# avoccado-nora-panel-teardropped.net
KiCad netlist of a schematic drawn in EAGLE
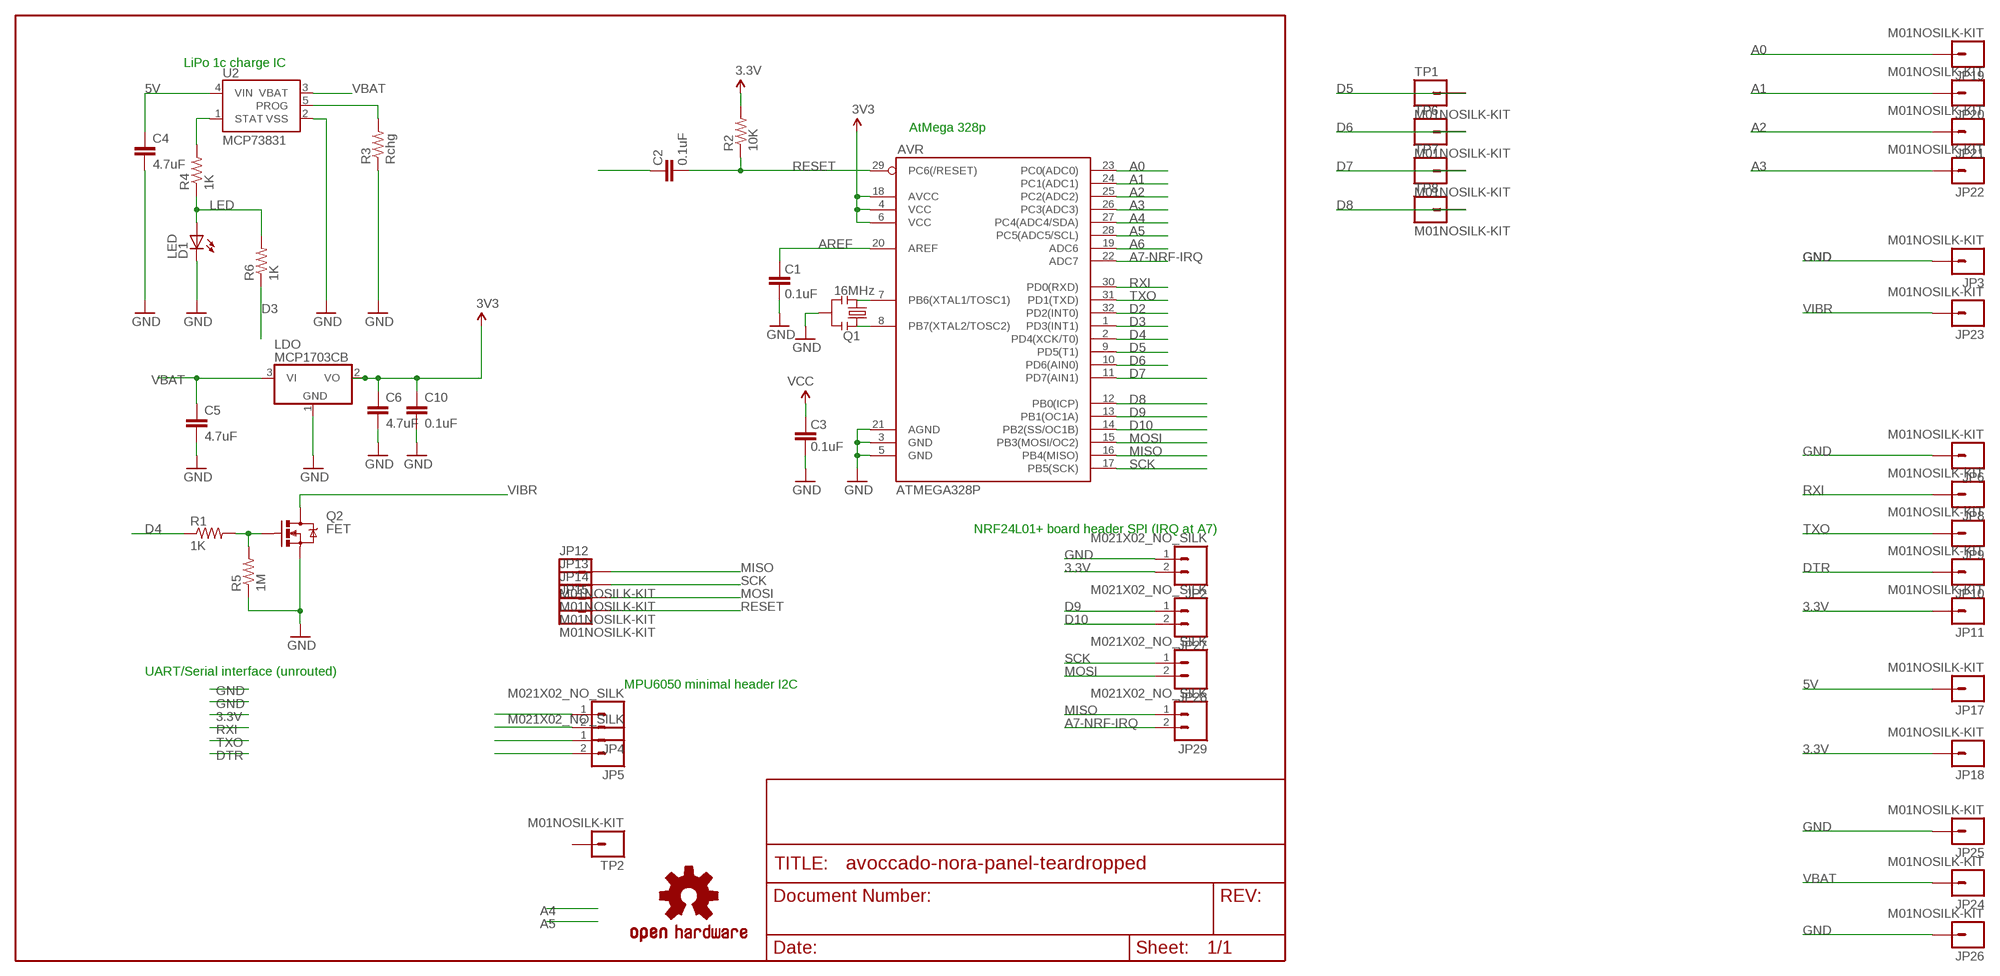
[diagram p0: schematic, sheet 1]

(export (version "E")
  (design (tool "Eeschema 10.0.6"))
  (components
    (comp (ref "AVR")
      (value "ATMEGA328P")
      (footprint "eagle-import:TQFP32-08")
      (libsource (lib "eagle-import") (part "ATMEGA328_SMT"))
    )
    (comp (ref "C1")
      (value "0.1uF")
      (footprint "eagle-import:C0402")
      (libsource (lib "eagle-import") (part "CAP0402"))
    )
    (comp (ref "C2")
      (value "0.1uF")
      (footprint "eagle-import:C0402")
      (libsource (lib "eagle-import") (part "CAP0402"))
    )
    (comp (ref "C3")
      (value "0.1uF")
      (footprint "eagle-import:C0402")
      (libsource (lib "eagle-import") (part "CAP0402"))
    )
    (comp (ref "C4")
      (value "4.7uF")
      (footprint "eagle-import:0603-CAP")
      (libsource (lib "eagle-import") (part "4.7UF-6.3V-10%(0603)0603"))
    )
    (comp (ref "C5")
      (value "4.7uF")
      (footprint "eagle-import:0603-CAP")
      (libsource (lib "eagle-import") (part "4.7UF-6.3V-10%(0603)0603"))
    )
    (comp (ref "C6")
      (value "4.7uF")
      (footprint "eagle-import:0603-CAP")
      (libsource (lib "eagle-import") (part "4.7UF-6.3V-10%(0603)0603"))
    )
    (comp (ref "C10")
      (value "0.1uF")
      (footprint "eagle-import:C0402")
      (libsource (lib "eagle-import") (part "CAP0402"))
    )
    (comp (ref "D1")
      (value "LED")
      (footprint "eagle-import:LED-0603")
      (libsource (lib "eagle-import") (part "LED0603"))
    )
    (comp (ref "JP2")
      (value "M021X02_NO_SILK")
      (footprint "eagle-import:1X02_NO_SILK")
      (libsource (lib "eagle-import") (part "M021X02_NO_SILK"))
    )
    (comp (ref "JP3")
      (value "M01NOSILK-KIT")
      (footprint "eagle-import:1X01NS-KIT")
      (libsource (lib "eagle-import") (part "M01NOSILK-KIT"))
    )
    (comp (ref "JP4")
      (value "M021X02_NO_SILK")
      (footprint "eagle-import:1X02_NO_SILK")
      (libsource (lib "eagle-import") (part "M021X02_NO_SILK"))
    )
    (comp (ref "JP5")
      (value "M021X02_NO_SILK")
      (footprint "eagle-import:1X02_NO_SILK")
      (libsource (lib "eagle-import") (part "M021X02_NO_SILK"))
    )
    (comp (ref "JP6")
      (value "M01NOSILK-KIT")
      (footprint "eagle-import:1X01NS-KIT")
      (libsource (lib "eagle-import") (part "M01NOSILK-KIT"))
    )
    (comp (ref "JP8")
      (value "M01NOSILK-KIT")
      (footprint "eagle-import:1X01NS-KIT")
      (libsource (lib "eagle-import") (part "M01NOSILK-KIT"))
    )
    (comp (ref "JP9")
      (value "M01NOSILK-KIT")
      (footprint "eagle-import:1X01NS-KIT")
      (libsource (lib "eagle-import") (part "M01NOSILK-KIT"))
    )
    (comp (ref "JP10")
      (value "M01NOSILK-KIT")
      (footprint "eagle-import:1X01NS-KIT")
      (libsource (lib "eagle-import") (part "M01NOSILK-KIT"))
    )
    (comp (ref "JP11")
      (value "M01NOSILK-KIT")
      (footprint "eagle-import:1X01NS-KIT")
      (libsource (lib "eagle-import") (part "M01NOSILK-KIT"))
    )
    (comp (ref "JP12")
      (value "M01NOSILK-KIT")
      (footprint "eagle-import:1X01NS-KIT")
      (libsource (lib "eagle-import") (part "M01NOSILK-KIT"))
    )
    (comp (ref "JP13")
      (value "M01NOSILK-KIT")
      (footprint "eagle-import:1X01NS-KIT")
      (libsource (lib "eagle-import") (part "M01NOSILK-KIT"))
    )
    (comp (ref "JP14")
      (value "M01NOSILK-KIT")
      (footprint "eagle-import:1X01NS-KIT")
      (libsource (lib "eagle-import") (part "M01NOSILK-KIT"))
    )
    (comp (ref "JP15")
      (value "M01NOSILK-KIT")
      (footprint "eagle-import:1X01NS-KIT")
      (libsource (lib "eagle-import") (part "M01NOSILK-KIT"))
    )
    (comp (ref "JP17")
      (value "M01NOSILK-KIT")
      (footprint "eagle-import:1X01NS-KIT")
      (libsource (lib "eagle-import") (part "M01NOSILK-KIT"))
    )
    (comp (ref "JP18")
      (value "M01NOSILK-KIT")
      (footprint "eagle-import:1X01NS-KIT")
      (libsource (lib "eagle-import") (part "M01NOSILK-KIT"))
    )
    (comp (ref "JP19")
      (value "M01NOSILK-KIT")
      (footprint "eagle-import:1X01NS-KIT")
      (libsource (lib "eagle-import") (part "M01NOSILK-KIT"))
    )
    (comp (ref "JP20")
      (value "M01NOSILK-KIT")
      (footprint "eagle-import:1X01NS-KIT")
      (libsource (lib "eagle-import") (part "M01NOSILK-KIT"))
    )
    (comp (ref "JP21")
      (value "M01NOSILK-KIT")
      (footprint "eagle-import:1X01NS-KIT")
      (libsource (lib "eagle-import") (part "M01NOSILK-KIT"))
    )
    (comp (ref "JP22")
      (value "M01NOSILK-KIT")
      (footprint "eagle-import:1X01NS-KIT")
      (libsource (lib "eagle-import") (part "M01NOSILK-KIT"))
    )
    (comp (ref "JP23")
      (value "M01NOSILK-KIT")
      (footprint "eagle-import:1X01NS-KIT")
      (libsource (lib "eagle-import") (part "M01NOSILK-KIT"))
    )
    (comp (ref "JP24")
      (value "M01NOSILK-KIT")
      (footprint "eagle-import:1X01NS-KIT")
      (libsource (lib "eagle-import") (part "M01NOSILK-KIT"))
    )
    (comp (ref "JP25")
      (value "M01NOSILK-KIT")
      (footprint "eagle-import:1X01NS-KIT")
      (libsource (lib "eagle-import") (part "M01NOSILK-KIT"))
    )
    (comp (ref "JP26")
      (value "M01NOSILK-KIT")
      (footprint "eagle-import:1X01NS-KIT")
      (libsource (lib "eagle-import") (part "M01NOSILK-KIT"))
    )
    (comp (ref "JP27")
      (value "M021X02_NO_SILK")
      (footprint "eagle-import:1X02_NO_SILK")
      (libsource (lib "eagle-import") (part "M021X02_NO_SILK"))
    )
    (comp (ref "JP28")
      (value "M021X02_NO_SILK")
      (footprint "eagle-import:1X02_NO_SILK")
      (libsource (lib "eagle-import") (part "M021X02_NO_SILK"))
    )
    (comp (ref "JP29")
      (value "M021X02_NO_SILK")
      (footprint "eagle-import:1X02_NO_SILK")
      (libsource (lib "eagle-import") (part "M021X02_NO_SILK"))
    )
    (comp (ref "LDO")
      (value "MCP1703CB")
      (footprint "eagle-import:SOT23")
      (libsource (lib "eagle-import") (part "MCP1703CB"))
    )
    (comp (ref "LOGO1")
      (value "OSHW-LOGOS")
      (footprint "eagle-import:OSHW-LOGO-S")
      (libsource (lib "eagle-import") (part "OSHW-LOGOS"))
    )
    (comp (ref "Q1")
      (value "16MHz")
      (footprint "eagle-import:RESONATOR-SMD")
      (libsource (lib "eagle-import") (part "RESONATORSMD"))
    )
    (comp (ref "Q2")
      (value "FET")
      (footprint "eagle-import:SOT323")
      (libsource (lib "eagle-import") (part "MOSFET-NCHANNEL2N7002PW"))
    )
    (comp (ref "R1")
      (value "1K")
      (footprint "eagle-import:0603-RES")
      (libsource (lib "eagle-import") (part "RESISTOR0603"))
    )
    (comp (ref "R2")
      (value "10K")
      (footprint "eagle-import:0603-RES")
      (libsource (lib "eagle-import") (part "RESISTOR0603"))
    )
    (comp (ref "R3")
      (value "Rchg")
      (footprint "eagle-import:0603-RES")
      (libsource (lib "eagle-import") (part "RESISTOR0603"))
    )
    (comp (ref "R4")
      (value "1K")
      (footprint "eagle-import:0603-RES")
      (libsource (lib "eagle-import") (part "RESISTOR0603"))
    )
    (comp (ref "R5")
      (value "1M")
      (footprint "eagle-import:0603-RES")
      (libsource (lib "eagle-import") (part "RESISTOR0603"))
    )
    (comp (ref "R6")
      (value "1K")
      (footprint "eagle-import:0603-RES")
      (libsource (lib "eagle-import") (part "RESISTOR0603"))
    )
    (comp (ref "TP1")
      (value "M01NOSILK-KIT")
      (footprint "eagle-import:1X01NS-KIT")
      (libsource (lib "eagle-import") (part "M01NOSILK-KIT"))
    )
    (comp (ref "TP2")
      (value "M01NOSILK-KIT")
      (footprint "eagle-import:1X01NS-KIT")
      (libsource (lib "eagle-import") (part "M01NOSILK-KIT"))
    )
    (comp (ref "TP6")
      (value "M01NOSILK-KIT")
      (footprint "eagle-import:1X01NS-KIT")
      (libsource (lib "eagle-import") (part "M01NOSILK-KIT"))
    )
    (comp (ref "TP7")
      (value "M01NOSILK-KIT")
      (footprint "eagle-import:1X01NS-KIT")
      (libsource (lib "eagle-import") (part "M01NOSILK-KIT"))
    )
    (comp (ref "TP8")
      (value "M01NOSILK-KIT")
      (footprint "eagle-import:1X01NS-KIT")
      (libsource (lib "eagle-import") (part "M01NOSILK-KIT"))
    )
    (comp (ref "U2")
      (value "MCP73831")
      (footprint "eagle-import:SOT23-5")
      (libsource (lib "eagle-import") (part "MCP73831"))
    )
  )
  (nets
    (net (code "1") (name "/5V") (class "Default")
      (node (ref "C4") (pin "1") (pinfunction "1_1") (pintype "passive"))
      (node (ref "JP17") (pin "1") (pinfunction "1_1") (pintype "passive"))
      (node (ref "U2") (pin "4") (pinfunction "VIN_4") (pintype "power_in"))
    )
    (net (code "2") (name "/A0") (class "Default")
      (node (ref "AVR") (pin "23") (pinfunction "PC0(ADC0)_23") (pintype "bidirectional"))
      (node (ref "JP19") (pin "1") (pinfunction "1_1") (pintype "passive"))
    )
    (net (code "3") (name "/A1") (class "Default")
      (node (ref "AVR") (pin "24") (pinfunction "PC1(ADC1)_24") (pintype "bidirectional"))
      (node (ref "JP20") (pin "1") (pinfunction "1_1") (pintype "passive"))
    )
    (net (code "4") (name "/A2") (class "Default")
      (node (ref "AVR") (pin "25") (pinfunction "PC2(ADC2)_25") (pintype "bidirectional"))
      (node (ref "JP21") (pin "1") (pinfunction "1_1") (pintype "passive"))
    )
    (net (code "5") (name "/A3") (class "Default")
      (node (ref "AVR") (pin "26") (pinfunction "PC3(ADC3)_26") (pintype "bidirectional"))
      (node (ref "JP22") (pin "1") (pinfunction "1_1") (pintype "passive"))
    )
    (net (code "6") (name "/A4") (class "Default")
      (node (ref "AVR") (pin "27") (pinfunction "PC4(ADC4/SDA)_27") (pintype "bidirectional"))
      (node (ref "JP5") (pin "2") (pinfunction "2_2") (pintype "passive"))
    )
    (net (code "7") (name "/A5") (class "Default")
      (node (ref "AVR") (pin "28") (pinfunction "PC5(ADC5/SCL)_28") (pintype "bidirectional"))
      (node (ref "JP5") (pin "1") (pinfunction "1_1") (pintype "passive"))
    )
    (net (code "8") (name "/A6") (class "Default")
      (node (ref "AVR") (pin "19") (pinfunction "ADC6_19") (pintype "bidirectional"))
    )
    (net (code "9") (name "/A7-NRF-IRQ") (class "Default")
      (node (ref "AVR") (pin "22") (pinfunction "ADC7_22") (pintype "bidirectional"))
      (node (ref "JP29") (pin "2") (pinfunction "2_2") (pintype "passive"))
    )
    (net (code "10") (name "/AREF") (class "Default")
      (node (ref "AVR") (pin "20") (pinfunction "AREF_20") (pintype "bidirectional"))
      (node (ref "C1") (pin "2") (pinfunction "2_2") (pintype "passive"))
    )
    (net (code "11") (name "/D2") (class "Default")
      (node (ref "AVR") (pin "32") (pinfunction "PD2(INT0)_32") (pintype "bidirectional"))
    )
    (net (code "12") (name "/D3") (class "Default")
      (node (ref "AVR") (pin "1") (pinfunction "PD3(INT1)_1") (pintype "bidirectional"))
      (node (ref "R6") (pin "1") (pinfunction "1_1") (pintype "passive"))
    )
    (net (code "13") (name "/D4") (class "Default")
      (node (ref "AVR") (pin "2") (pinfunction "PD4(XCK/T0)_2") (pintype "bidirectional"))
      (node (ref "R1") (pin "1") (pinfunction "1_1") (pintype "passive"))
    )
    (net (code "14") (name "/D5") (class "Default")
      (node (ref "AVR") (pin "9") (pinfunction "PD5(T1)_9") (pintype "bidirectional"))
      (node (ref "TP1") (pin "1") (pinfunction "1_1") (pintype "passive"))
    )
    (net (code "15") (name "/D6") (class "Default")
      (node (ref "AVR") (pin "10") (pinfunction "PD6(AIN0)_10") (pintype "bidirectional"))
      (node (ref "TP6") (pin "1") (pinfunction "1_1") (pintype "passive"))
    )
    (net (code "16") (name "/D7") (class "Default")
      (node (ref "AVR") (pin "11") (pinfunction "PD7(AIN1)_11") (pintype "bidirectional"))
      (node (ref "TP7") (pin "1") (pinfunction "1_1") (pintype "passive"))
    )
    (net (code "17") (name "/D8") (class "Default")
      (node (ref "AVR") (pin "12") (pinfunction "PB0(ICP)_12") (pintype "bidirectional"))
      (node (ref "TP8") (pin "1") (pinfunction "1_1") (pintype "passive"))
    )
    (net (code "18") (name "/D9") (class "Default")
      (node (ref "AVR") (pin "13") (pinfunction "PB1(OC1A)_13") (pintype "bidirectional"))
      (node (ref "JP27") (pin "1") (pinfunction "1_1") (pintype "passive"))
    )
    (net (code "19") (name "/D10") (class "Default")
      (node (ref "AVR") (pin "14") (pinfunction "PB2(SS/OC1B)_14") (pintype "bidirectional"))
      (node (ref "JP27") (pin "2") (pinfunction "2_2") (pintype "passive"))
    )
    (net (code "20") (name "/DTR") (class "Default")
      (node (ref "C2") (pin "2") (pinfunction "2_2") (pintype "passive"))
      (node (ref "JP10") (pin "1") (pinfunction "1_1") (pintype "passive"))
    )
    (net (code "21") (name "/LED") (class "Default")
      (node (ref "D1") (pin "A") (pinfunction "A_A") (pintype "passive"))
      (node (ref "R4") (pin "1") (pinfunction "1_1") (pintype "passive"))
      (node (ref "R6") (pin "2") (pinfunction "2_2") (pintype "passive"))
    )
    (net (code "22") (name "/MISO") (class "Default")
      (node (ref "AVR") (pin "16") (pinfunction "PB4(MISO)_16") (pintype "bidirectional"))
      (node (ref "JP12") (pin "1") (pinfunction "1_1") (pintype "passive"))
      (node (ref "JP29") (pin "1") (pinfunction "1_1") (pintype "passive"))
    )
    (net (code "23") (name "/MOSI") (class "Default")
      (node (ref "AVR") (pin "15") (pinfunction "PB3(MOSI/OC2)_15") (pintype "bidirectional"))
      (node (ref "JP14") (pin "1") (pinfunction "1_1") (pintype "passive"))
      (node (ref "JP28") (pin "2") (pinfunction "2_2") (pintype "passive"))
    )
    (net (code "24") (name "/RESET") (class "Default")
      (node (ref "AVR") (pin "29") (pinfunction "PC6(/RESET)_29") (pintype "bidirectional"))
      (node (ref "C2") (pin "1") (pinfunction "1_1") (pintype "passive"))
      (node (ref "JP15") (pin "1") (pinfunction "1_1") (pintype "passive"))
      (node (ref "R2") (pin "1") (pinfunction "1_1") (pintype "passive"))
    )
    (net (code "25") (name "/RXI") (class "Default")
      (node (ref "AVR") (pin "30") (pinfunction "PD0(RXD)_30") (pintype "bidirectional"))
      (node (ref "JP8") (pin "1") (pinfunction "1_1") (pintype "passive"))
    )
    (net (code "26") (name "/SCK") (class "Default")
      (node (ref "AVR") (pin "17") (pinfunction "PB5(SCK)_17") (pintype "bidirectional"))
      (node (ref "JP13") (pin "1") (pinfunction "1_1") (pintype "passive"))
      (node (ref "JP28") (pin "1") (pinfunction "1_1") (pintype "passive"))
    )
    (net (code "27") (name "/TXO") (class "Default")
      (node (ref "AVR") (pin "31") (pinfunction "PD1(TXD)_31") (pintype "bidirectional"))
      (node (ref "JP9") (pin "1") (pinfunction "1_1") (pintype "passive"))
    )
    (net (code "28") (name "/VBAT") (class "Default")
      (node (ref "C5") (pin "1") (pinfunction "1_1") (pintype "passive"))
      (node (ref "JP24") (pin "1") (pinfunction "1_1") (pintype "passive"))
      (node (ref "LDO") (pin "3") (pinfunction "VI_3") (pintype "input"))
      (node (ref "U2") (pin "3") (pinfunction "VBAT_3") (pintype "power_in"))
    )
    (net (code "29") (name "/VIBR") (class "Default")
      (node (ref "JP23") (pin "1") (pinfunction "1_1") (pintype "passive"))
      (node (ref "Q2") (pin "3") (pinfunction "D_3") (pintype "passive"))
    )
    (net (code "30") (name "3.3V") (class "Default")
      (node (ref "AVR") (pin "18") (pinfunction "AVCC_18") (pintype "bidirectional"))
      (node (ref "AVR") (pin "4") (pinfunction "VCC_4") (pintype "bidirectional"))
      (node (ref "AVR") (pin "6") (pinfunction "VCC_6") (pintype "bidirectional"))
      (node (ref "C10") (pin "1") (pinfunction "1_1") (pintype "passive"))
      (node (ref "C3") (pin "2") (pinfunction "2_2") (pintype "passive"))
      (node (ref "C6") (pin "1") (pinfunction "1_1") (pintype "passive"))
      (node (ref "JP11") (pin "1") (pinfunction "1_1") (pintype "passive"))
      (node (ref "JP18") (pin "1") (pinfunction "1_1") (pintype "passive"))
      (node (ref "JP2") (pin "2") (pinfunction "2_2") (pintype "passive"))
      (node (ref "JP4") (pin "1") (pinfunction "1_1") (pintype "passive"))
      (node (ref "LDO") (pin "2") (pinfunction "VO_2") (pintype "passive"))
      (node (ref "R2") (pin "2") (pinfunction "2_2") (pintype "passive"))
    )
    (net (code "31") (name "GND") (class "Default")
      (node (ref "AVR") (pin "21") (pinfunction "AGND_21") (pintype "bidirectional"))
      (node (ref "AVR") (pin "3") (pinfunction "GND_3") (pintype "bidirectional"))
      (node (ref "AVR") (pin "5") (pinfunction "GND_5") (pintype "bidirectional"))
      (node (ref "C1") (pin "1") (pinfunction "1_1") (pintype "passive"))
      (node (ref "C10") (pin "2") (pinfunction "2_2") (pintype "passive"))
      (node (ref "C3") (pin "1") (pinfunction "1_1") (pintype "passive"))
      (node (ref "C4") (pin "2") (pinfunction "2_2") (pintype "passive"))
      (node (ref "C5") (pin "2") (pinfunction "2_2") (pintype "passive"))
      (node (ref "C6") (pin "2") (pinfunction "2_2") (pintype "passive"))
      (node (ref "D1") (pin "C") (pinfunction "C_C") (pintype "passive"))
      (node (ref "JP2") (pin "1") (pinfunction "1_1") (pintype "passive"))
      (node (ref "JP25") (pin "1") (pinfunction "1_1") (pintype "passive"))
      (node (ref "JP26") (pin "1") (pinfunction "1_1") (pintype "passive"))
      (node (ref "JP3") (pin "1") (pinfunction "1_1") (pintype "passive"))
      (node (ref "JP4") (pin "2") (pinfunction "2_2") (pintype "passive"))
      (node (ref "JP6") (pin "1") (pinfunction "1_1") (pintype "passive"))
      (node (ref "LDO") (pin "1") (pinfunction "GND_1") (pintype "passive"))
      (node (ref "Q1") (pin "2") (pinfunction "2_2") (pintype "passive"))
      (node (ref "Q2") (pin "2") (pinfunction "S_2") (pintype "passive"))
      (node (ref "R3") (pin "1") (pinfunction "1_1") (pintype "passive"))
      (node (ref "R5") (pin "1") (pinfunction "1_1") (pintype "passive"))
      (node (ref "U2") (pin "2") (pinfunction "VSS_2") (pintype "power_in"))
    )
    (net (code "32") (name "Net-(AVR-PB6(XTAL1{slash}TOSC1))") (class "Default")
      (node (ref "AVR") (pin "7") (pinfunction "PB6(XTAL1/TOSC1)_7") (pintype "bidirectional"))
      (node (ref "Q1") (pin "3") (pinfunction "3_3") (pintype "passive"))
    )
    (net (code "33") (name "Net-(AVR-PB7(XTAL2{slash}TOSC2))") (class "Default")
      (node (ref "AVR") (pin "8") (pinfunction "PB7(XTAL2/TOSC2)_8") (pintype "bidirectional"))
      (node (ref "Q1") (pin "1") (pinfunction "1_1") (pintype "passive"))
    )
    (net (code "34") (name "Net-(Q2-G)") (class "Default")
      (node (ref "Q2") (pin "1") (pinfunction "G_1") (pintype "passive"))
      (node (ref "R1") (pin "2") (pinfunction "2_2") (pintype "passive"))
      (node (ref "R5") (pin "2") (pinfunction "2_2") (pintype "passive"))
    )
    (net (code "35") (name "Net-(U2-PROG)") (class "Default")
      (node (ref "R3") (pin "2") (pinfunction "2_2") (pintype "passive"))
      (node (ref "U2") (pin "5") (pinfunction "PROG_5") (pintype "input"))
    )
    (net (code "36") (name "Net-(U2-STAT)") (class "Default")
      (node (ref "R4") (pin "2") (pinfunction "2_2") (pintype "passive"))
      (node (ref "U2") (pin "1") (pinfunction "STAT_1") (pintype "output"))
    )
    (net (code "37") (name "unconnected-(TP2-Pad1)") (class "Default")
      (node (ref "TP2") (pin "1") (pinfunction "1_1") (pintype "passive"))
    )
  )
)
